# nRF_52840.net
KiCad netlist of a schematic drawn in Altium Designer
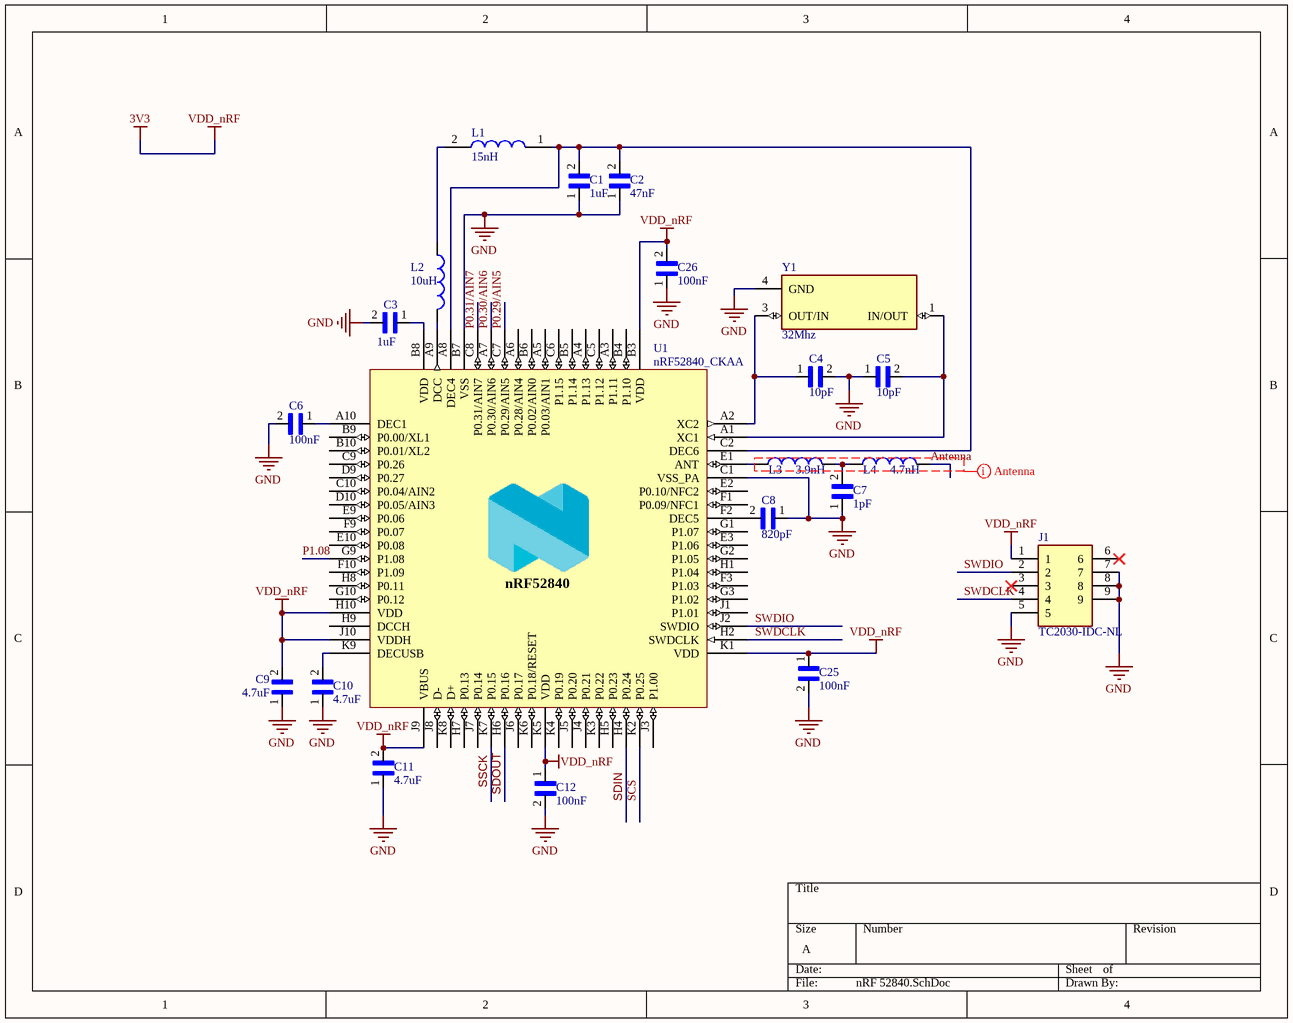
[diagram p0: nRF 52840.SchDoc]

(export (version "E")
  (design (tool "Eeschema 10.0.6"))
  (components
    (comp (ref "C1")
      (value "1uF")
      (footprint "CAPC1608X90N")
      (fields
        (field (name "MANUFACTURER") "TDK")
        (field (name "MANUFACTURER PART NUMBER") "C1608X7R1C105K080AC")
        (field (name "TOLERANCE") "10%")
      )
      (libsource (lib "SnapEDA_Library") (part "C1608X7R1C105K080AC"))
    )
    (comp (ref "C2")
      (value "47nF")
      (footprint "CAPC0603X33N")
      (description "0201 47 nF 16 V ±10% Tolerance X5R SMT Multilayer Ceramic Capacitor")
      (fields
        (field (name "MANUFACTURER") "Murata")
        (field (name "MANUFACTURER PART NUMBER") "GRM033R61C473KE84D")
      )
      (libsource (lib "SnapEDA_Library") (part "GRM033R61C473KE84D"))
    )
    (comp (ref "C3")
      (value "1uF")
      (footprint "CAPC1608X90N")
      (fields
        (field (name "MANUFACTURER") "TDK")
        (field (name "MANUFACTURER PART NUMBER") "C1608X7R1C105K080AC")
        (field (name "TOLERANCE") "10%")
      )
      (libsource (lib "") (part "C1608X7R1C105K080AC_1"))
    )
    (comp (ref "C4")
      (value "10pF")
      (footprint "CAPC0603X33N")
      (description "Cap Ceramic 10pF 100V C0G 5% Pad SMD 0201 125C T/R")
      (fields
        (field (name "MANUFACTURER") "Murata")
        (field (name "MANUFACTURER PART NUMBER") "GRM0335C2A100JA01D")
      )
      (libsource (lib "SnapEDA_Library") (part "GRM0335C2A100JA01D"))
    )
    (comp (ref "C5")
      (value "10pF")
      (footprint "CAPC0603X33N")
      (description "Cap Ceramic 10pF 100V C0G 5% Pad SMD 0201 125C T/R")
      (fields
        (field (name "MANUFACTURER") "Murata")
        (field (name "MANUFACTURER PART NUMBER") "GRM0335C2A100JA01D")
      )
      (libsource (lib "SnapEDA_Library") (part "GRM0335C2A100JA01D"))
    )
    (comp (ref "C6")
      (value "100nF")
      (footprint "CAPC1608X90N")
      (description "0603 100 nF 25 V -20 / +80 % Tolerance Y5V SMT Multilayer Ceramic Capacitor")
      (fields
        (field (name "MANUFACTURER") "Kyocera AVX")
        (field (name "MANUFACTURER PART NUMBER") "06033G104ZAT2A")
      )
      (libsource (lib "SnapEDA_Library") (part "06033G104ZAT2A"))
    )
    (comp (ref "C7")
      (value "1pF")
      (footprint "CAPC0603X33N")
      (description "0201 1 pF 50 V ±0.1 pF Tolerance C0G SMT Multilayer Ceramic Capacitor")
      (fields
        (field (name "MANUFACTURER") "Murata")
        (field (name "MANUFACTURER PART NUMBER") "GRM0335C1H1R0BA01D")
      )
      (libsource (lib "SnapEDA_Library") (part "GRM0335C1H1R0BA01D"))
    )
    (comp (ref "C8")
      (value "820pF")
      (footprint "CAPC0603X33N")
      (description "0201 820 pF 25 V ±10% Tolerance X7R Multilayer Ceramic Capacitor")
      (fields
        (field (name "MANUFACTURER") "Murata")
        (field (name "MANUFACTURER PART NUMBER") "GRM033R71E821KA01D")
      )
      (libsource (lib "SnapEDA_Library") (part "GRM033R71E821KA01D"))
    )
    (comp (ref "C9")
      (value "4.7uF")
      (footprint "CAPC1608X95N")
      (description "0603 4.7 uF 10 V ±10% Tolerance X7S Multilayer Ceramic Capacitor")
      (fields
        (field (name "MANUFACTURER") "Murata")
        (field (name "MANUFACTURER PART NUMBER") "GRM188C71A475KE11D")
      )
      (libsource (lib "SnapEDA_Library") (part "GRM188C71A475KE11D"))
    )
    (comp (ref "C10")
      (value "4.7uF")
      (footprint "CAPC1608X95N")
      (description "0603 4.7 uF 10 V ±10% Tolerance X7S Multilayer Ceramic Capacitor")
      (fields
        (field (name "MANUFACTURER") "Murata")
        (field (name "MANUFACTURER PART NUMBER") "GRM188C71A475KE11D")
      )
      (libsource (lib "SnapEDA_Library") (part "GRM188C71A475KE11D"))
    )
    (comp (ref "C11")
      (value "4.7uF")
      (footprint "CAPC1608X95N")
      (description "0603 4.7 uF 10 V ±10% Tolerance X7S Multilayer Ceramic Capacitor")
      (fields
        (field (name "MANUFACTURER") "Murata")
        (field (name "MANUFACTURER PART NUMBER") "GRM188C71A475KE11D")
      )
      (libsource (lib "SnapEDA_Library") (part "GRM188C71A475KE11D"))
    )
    (comp (ref "C12")
      (value "100nF")
      (footprint "CAPC1005X55N")
      (description "Cap Ceramic 0.1uF 25V X5R 10% Pad SMD 0402 85°C T/R / Multi Layer Ceramic Capacitor (MLCC)")
      (fields
        (field (name "MANUFACTURER") "Samsung")
        (field (name "MANUFACTURER PART NUMBER") "CL05A104KA5NNNC")
      )
      (libsource (lib "SnapEDA_Library") (part "CL05A104KA5NNNC"))
    )
    (comp (ref "C25")
      (value "100nF")
      (footprint "CAPC1005X55N")
      (description "Cap Ceramic 0.1uF 25V X5R 10% Pad SMD 0402 85°C T/R / Multi Layer Ceramic Capacitor (MLCC)")
      (fields
        (field (name "MANUFACTURER") "Samsung")
        (field (name "MANUFACTURER PART NUMBER") "CL05A104KA5NNNC")
      )
      (libsource (lib "SnapEDA_Library") (part "CL05A104KA5NNNC"))
    )
    (comp (ref "C26")
      (value "100nF")
      (footprint "CAPC1005X55N")
      (description "Cap Ceramic 0.1uF 25V X5R 10% Pad SMD 0402 85°C T/R / Multi Layer Ceramic Capacitor (MLCC)")
      (fields
        (field (name "MANUFACTURER") "Samsung")
        (field (name "MANUFACTURER PART NUMBER") "CL05A104KA5NNNC")
      )
      (libsource (lib "") (part "CL05A104KA5NNNC_1"))
    )
    (comp (ref "J1")
      (value "TC2030-IDC-NL")
      (footprint "SamacSys:TC2030IDCNL")
      (description "Connector")
      (libsource (lib "*") (part "TC2030-IDC-NL"))
    )
    (comp (ref "L1")
      (value "15nH")
      (footprint "SamacSys:LQG15WH0N7B02D")
      (description "Inductor RF Chip Multi-Layer 15nH 5% 100MHz 8Q-Factor Air 300mA 460mOhm DCR 0402 Paper T/R")
      (fields
        (field (name "MANUFACTURER") "Murata")
        (field (name "MANUFACTURER PART NUMBER") "LQG15HN15NJ02D")
      )
      (libsource (lib "*") (part "LQG15HN15NJ02D"))
    )
    (comp (ref "L2")
      (value "10uH")
      (footprint "INDC1608X100N")
      (description "Inductor Chip Wirewound 10uH 10% 2.52MHz Ferrite 80mA 468mOhm DCR 0603 T/R")
      (fields
        (field (name "MANUFACTURER") "Taiyo Yuden")
        (field (name "MANUFACTURER PART NUMBER") "LBMF1608T100K")
      )
      (libsource (lib "SnapEDA_Library") (part "LBMF1608T100K"))
    )
    (comp (ref "L3")
      (value "3.9nH")
      (footprint "INDC0603X33N")
      (description "Inductor RF Chip Thin Film 3.9nH 0.1nH 500MHz 14Q-Factor 400mA 300mOhm DCR 0201 Paper T/R")
      (fields
        (field (name "MANUFACTURER") "Murata")
        (field (name "MANUFACTURER PART NUMBER") "LQP03TN3N9B02D")
      )
      (libsource (lib "Flex PCB") (part "LQP03TN3N9B02D"))
    )
    (comp (ref "L4")
      (value "4.7nH")
      (footprint "INDC0603X33N")
      (description "Inductor RF Chip Thin Film 4.7nH 3% 500MHz 14Q-Factor 350mA 400mOhm DCR 0201 Paper T/R")
      (fields (field (name "MF") "{'manufacturer': u'Murata'}") (field (name "MANUFACTURER") "Murata"))
      (libsource (lib "Flex PCB") (part "LQP03TN4N7H02D"))
    )
    (comp (ref "U1")
      (value "nRF52840_CKAA")
      (footprint "BGA94C35P10X10_352X356X50")
      (description "Multi-protocol Bluetooth Low Energy, IEEE 802.15.4, ANT and 2.4GHz proprietary system-on-chip")
      (fields
        (field (name "MANUFACTURER") "Nordic Semiconductor")
        (field (name "MANUFACTURER PART NUMBER") "nRF52840-CKAAD0")
        (field (name "PUBLISHER") "Nordic Semiconductor")
      )
      (libsource (lib "nrf52840_ckaa") (part "nRF52840_CKAA"))
    )
    (comp (ref "Y1")
      (value "32Mhz")
      (footprint "XTAL_ECS-374-8-48-CKY-TR")
      (description "Crystal 32MHz ±10ppm (Tol) ±10ppm (Stability) 10pF 100Ohm 4-Pin Ultra Mini-CSMD T/R")
      (fields
        (field (name "MANUFACTURER") "ECS International")
        (field (name "MANUFACTURER PART NUMBER") "ECS-320-10-48-CKY-TR")
      )
      (libsource (lib "SnapEDA_Library") (part "ECS-320-10-48-CKY-TR"))
    )
  )
  (nets
    (net (code "1") (name "/Antenna") (class "Default")
      (node (ref "L4") (pin "2") (pinfunction "2_2") (pintype "passive"))
    )
    (net (code "2") (name "/P0.29{slash}AIN5") (class "Default")
      (node (ref "U1") (pin "C7") (pinfunction "P0.29/AIN5_C7") (pintype "bidirectional"))
    )
    (net (code "3") (name "/P0.30{slash}AIN6") (class "Default")
      (node (ref "U1") (pin "A7") (pinfunction "P0.30/AIN6_A7") (pintype "bidirectional"))
    )
    (net (code "4") (name "/P0.31{slash}AIN7") (class "Default")
      (node (ref "U1") (pin "C8") (pinfunction "P0.31/AIN7_C8") (pintype "bidirectional"))
    )
    (net (code "5") (name "/P1.08") (class "Default")
      (node (ref "U1") (pin "G9") (pinfunction "P1.08_G9") (pintype "bidirectional"))
    )
    (net (code "6") (name "/SCS") (class "Default")
      (node (ref "U1") (pin "K2") (pinfunction "P0.25_K2") (pintype "bidirectional"))
    )
    (net (code "7") (name "/SDIN") (class "Default")
      (node (ref "U1") (pin "H4") (pinfunction "P0.24_H4") (pintype "bidirectional"))
    )
    (net (code "8") (name "/SDOUT") (class "Default")
      (node (ref "U1") (pin "H6") (pinfunction "P0.16_H6") (pintype "bidirectional"))
    )
    (net (code "9") (name "/SSCK") (class "Default")
      (node (ref "U1") (pin "K7") (pinfunction "P0.15_K7") (pintype "bidirectional"))
    )
    (net (code "10") (name "/SWDCLK") (class "Default")
      (node (ref "J1") (pin "4") (pinfunction "4_4") (pintype "passive"))
      (node (ref "U1") (pin "H2") (pinfunction "SWDCLK_H2") (pintype "input"))
    )
    (net (code "11") (name "/SWDIO") (class "Default")
      (node (ref "J1") (pin "2") (pinfunction "2_2") (pintype "passive"))
      (node (ref "U1") (pin "J2") (pinfunction "SWDIO_J2") (pintype "bidirectional"))
    )
    (net (code "12") (name "3V3") (class "Default")
      (node (ref "C11") (pin "2") (pinfunction "2_2") (pintype "passive"))
      (node (ref "C12") (pin "1") (pinfunction "1_1") (pintype "passive"))
      (node (ref "C25") (pin "1") (pinfunction "1_1") (pintype "passive"))
      (node (ref "C26") (pin "2") (pinfunction "2_2") (pintype "passive"))
      (node (ref "C9") (pin "2") (pinfunction "2_2") (pintype "passive"))
      (node (ref "J1") (pin "1") (pinfunction "1_1") (pintype "passive"))
      (node (ref "U1") (pin "B3") (pinfunction "VDD_B3") (pintype "power_in"))
      (node (ref "U1") (pin "H10") (pinfunction "VDD_H10") (pintype "power_in"))
      (node (ref "U1") (pin "J10") (pinfunction "VDDH_J10") (pintype "power_in"))
      (node (ref "U1") (pin "J9") (pinfunction "VBUS_J9") (pintype "power_in"))
      (node (ref "U1") (pin "K1") (pinfunction "VDD_K1") (pintype "power_in"))
      (node (ref "U1") (pin "K5") (pinfunction "VDD_K5") (pintype "power_in"))
    )
    (net (code "13") (name "GND") (class "Default")
      (node (ref "C1") (pin "1") (pinfunction "1_1") (pintype "passive"))
      (node (ref "C10") (pin "1") (pinfunction "1_1") (pintype "passive"))
      (node (ref "C11") (pin "1") (pinfunction "1_1") (pintype "passive"))
      (node (ref "C12") (pin "2") (pinfunction "2_2") (pintype "passive"))
      (node (ref "C2") (pin "1") (pinfunction "1_1") (pintype "passive"))
      (node (ref "C25") (pin "2") (pinfunction "2_2") (pintype "passive"))
      (node (ref "C26") (pin "1") (pinfunction "1_1") (pintype "passive"))
      (node (ref "C3") (pin "2") (pinfunction "2_2") (pintype "passive"))
      (node (ref "C4") (pin "2") (pinfunction "2_2") (pintype "passive"))
      (node (ref "C5") (pin "1") (pinfunction "1_1") (pintype "passive"))
      (node (ref "C6") (pin "2") (pinfunction "2_2") (pintype "passive"))
      (node (ref "C7") (pin "1") (pinfunction "1_1") (pintype "passive"))
      (node (ref "C8") (pin "1") (pinfunction "1_1") (pintype "passive"))
      (node (ref "C9") (pin "1") (pinfunction "1_1") (pintype "passive"))
      (node (ref "J1") (pin "5") (pinfunction "5_5") (pintype "passive"))
      (node (ref "J1") (pin "7") (pinfunction "7_7") (pintype "passive"))
      (node (ref "J1") (pin "8") (pinfunction "8_8") (pintype "passive"))
      (node (ref "J1") (pin "9") (pinfunction "9_9") (pintype "passive"))
      (node (ref "U1") (pin "B7") (pinfunction "VSS_B7") (pintype "power_in"))
      (node (ref "U1") (pin "C1") (pinfunction "VSS_PA_C1") (pintype "power_in"))
      (node (ref "U1") (pin "C4") (pinfunction "GND_C4") (pintype "power_in"))
      (node (ref "U1") (pin "D3") (pinfunction "GND_D3") (pintype "power_in"))
      (node (ref "U1") (pin "D4") (pinfunction "GND_D4") (pintype "power_in"))
      (node (ref "U1") (pin "D5") (pinfunction "GND_D5") (pintype "power_in"))
      (node (ref "U1") (pin "D6") (pinfunction "GND_D6") (pintype "power_in"))
      (node (ref "U1") (pin "D7") (pinfunction "GND_D7") (pintype "power_in"))
      (node (ref "U1") (pin "D8") (pinfunction "GND_D8") (pintype "power_in"))
      (node (ref "U1") (pin "E4") (pinfunction "GND_E4") (pintype "power_in"))
      (node (ref "U1") (pin "E5") (pinfunction "GND_E5") (pintype "power_in"))
      (node (ref "U1") (pin "E6") (pinfunction "GND_E6") (pintype "power_in"))
      (node (ref "U1") (pin "E7") (pinfunction "GND_E7") (pintype "power_in"))
      (node (ref "U1") (pin "E8") (pinfunction "GND_E8") (pintype "power_in"))
      (node (ref "U1") (pin "F4") (pinfunction "GND_F4") (pintype "power_in"))
      (node (ref "U1") (pin "F5") (pinfunction "GND_F5") (pintype "power_in"))
      (node (ref "U1") (pin "F6") (pinfunction "GND_F6") (pintype "power_in"))
      (node (ref "U1") (pin "F7") (pinfunction "GND_F7") (pintype "power_in"))
      (node (ref "U1") (pin "F8") (pinfunction "GND_F8") (pintype "power_in"))
      (node (ref "U1") (pin "G4") (pinfunction "GND_G4") (pintype "power_in"))
      (node (ref "U1") (pin "G5") (pinfunction "GND_G5") (pintype "power_in"))
      (node (ref "U1") (pin "G6") (pinfunction "GND_G6") (pintype "power_in"))
      (node (ref "U1") (pin "G7") (pinfunction "GND_G7") (pintype "power_in"))
      (node (ref "U1") (pin "G8") (pinfunction "GND_G8") (pintype "power_in"))
      (node (ref "U1") (pin "K10") (pinfunction "GND_K10") (pintype "power_in"))
      (node (ref "Y1") (pin "4") (pinfunction "GND_4") (pintype "power_in"))
    )
    (net (code "14") (name "Net-(C3-Pad1)") (class "Default")
      (node (ref "C3") (pin "1") (pinfunction "1_1") (pintype "passive"))
      (node (ref "U1") (pin "B8") (pinfunction "VDD_B8") (pintype "power_in"))
    )
    (net (code "15") (name "Net-(C7-Pad2)") (class "Default")
      (node (ref "C7") (pin "2") (pinfunction "2_2") (pintype "passive"))
      (node (ref "L3") (pin "2") (pinfunction "2_2") (pintype "passive"))
      (node (ref "L4") (pin "1") (pinfunction "1_1") (pintype "passive"))
    )
    (net (code "16") (name "Net-(L1-Pad2)") (class "Default")
      (node (ref "L1") (pin "2") (pinfunction "2_2") (pintype "passive"))
      (node (ref "L2") (pin "1") (pinfunction "1_1") (pintype "passive"))
    )
    (net (code "17") (name "Net-(U1-ANT)") (class "Default")
      (node (ref "L3") (pin "1") (pinfunction "1_1") (pintype "passive"))
      (node (ref "U1") (pin "E1") (pinfunction "ANT_E1") (pintype "bidirectional"))
    )
    (net (code "18") (name "Net-(U1-DCC)") (class "Default")
      (node (ref "L2") (pin "2") (pinfunction "2_2") (pintype "passive"))
      (node (ref "U1") (pin "A9") (pinfunction "DCC_A9") (pintype "output"))
    )
    (net (code "19") (name "Net-(U1-DEC1)") (class "Default")
      (node (ref "C6") (pin "1") (pinfunction "1_1") (pintype "passive"))
      (node (ref "U1") (pin "A10") (pinfunction "DEC1_A10") (pintype "power_in"))
    )
    (net (code "20") (name "Net-(U1-DEC4)") (class "Default")
      (node (ref "C1") (pin "2") (pinfunction "2_2") (pintype "passive"))
      (node (ref "C2") (pin "2") (pinfunction "2_2") (pintype "passive"))
      (node (ref "L1") (pin "1") (pinfunction "1_1") (pintype "passive"))
      (node (ref "U1") (pin "A8") (pinfunction "DEC4_A8") (pintype "power_in"))
      (node (ref "U1") (pin "C2") (pinfunction "DEC6_C2") (pintype "power_in"))
    )
    (net (code "21") (name "Net-(U1-DEC5)") (class "Default")
      (node (ref "C8") (pin "2") (pinfunction "2_2") (pintype "passive"))
      (node (ref "U1") (pin "F2") (pinfunction "DEC5_F2") (pintype "power_in"))
    )
    (net (code "22") (name "Net-(U1-DECUSB)") (class "Default")
      (node (ref "C10") (pin "2") (pinfunction "2_2") (pintype "passive"))
      (node (ref "U1") (pin "K9") (pinfunction "DECUSB_K9") (pintype "power_in"))
    )
    (net (code "23") (name "Net-(U1-XC1)") (class "Default")
      (node (ref "C5") (pin "2") (pinfunction "2_2") (pintype "passive"))
      (node (ref "U1") (pin "A1") (pinfunction "XC1_A1") (pintype "input"))
      (node (ref "Y1") (pin "1") (pinfunction "IN/OUT_1") (pintype "bidirectional"))
    )
    (net (code "24") (name "Net-(U1-XC2)") (class "Default")
      (node (ref "C4") (pin "1") (pinfunction "1_1") (pintype "passive"))
      (node (ref "U1") (pin "A2") (pinfunction "XC2_A2") (pintype "output"))
      (node (ref "Y1") (pin "3") (pinfunction "OUT/IN_3") (pintype "bidirectional"))
    )
    (net (code "25") (name "unconnected-(J1-Pad3)") (class "Default")
      (node (ref "J1") (pin "3") (pinfunction "3_3") (pintype "passive+no_connect"))
    )
    (net (code "26") (name "unconnected-(J1-Pad6)") (class "Default")
      (node (ref "J1") (pin "6") (pinfunction "6_6") (pintype "passive+no_connect"))
    )
    (net (code "27") (name "unconnected-(U1-D+-PadK8)") (class "Default")
      (node (ref "U1") (pin "K8") (pinfunction "D+_K8") (pintype "bidirectional"))
    )
    (net (code "28") (name "unconnected-(U1-D--PadJ8)") (class "Default")
      (node (ref "U1") (pin "J8") (pinfunction "D-_J8") (pintype "bidirectional"))
    )
    (net (code "29") (name "unconnected-(U1-DCCH-PadH9)") (class "Default")
      (node (ref "U1") (pin "H9") (pinfunction "DCCH_H9") (pintype "power_in"))
    )
    (net (code "30") (name "unconnected-(U1-P0.00{slash}XL1-PadB9)") (class "Default")
      (node (ref "U1") (pin "B9") (pinfunction "P0.00/XL1_B9") (pintype "bidirectional"))
    )
    (net (code "31") (name "unconnected-(U1-P0.01{slash}XL2-PadB10)") (class "Default")
      (node (ref "U1") (pin "B10") (pinfunction "P0.01/XL2_B10") (pintype "bidirectional"))
    )
    (net (code "32") (name "unconnected-(U1-P0.02{slash}AIN0-PadB6)") (class "Default")
      (node (ref "U1") (pin "B6") (pinfunction "P0.02/AIN0_B6") (pintype "bidirectional"))
    )
    (net (code "33") (name "unconnected-(U1-P0.03{slash}AIN1-PadA5)") (class "Default")
      (node (ref "U1") (pin "A5") (pinfunction "P0.03/AIN1_A5") (pintype "bidirectional"))
    )
    (net (code "34") (name "unconnected-(U1-P0.04{slash}AIN2-PadC10)") (class "Default")
      (node (ref "U1") (pin "C10") (pinfunction "P0.04/AIN2_C10") (pintype "bidirectional"))
    )
    (net (code "35") (name "unconnected-(U1-P0.05{slash}AIN3-PadD10)") (class "Default")
      (node (ref "U1") (pin "D10") (pinfunction "P0.05/AIN3_D10") (pintype "bidirectional"))
    )
    (net (code "36") (name "unconnected-(U1-P0.06-PadE9)") (class "Default")
      (node (ref "U1") (pin "E9") (pinfunction "P0.06_E9") (pintype "bidirectional"))
    )
    (net (code "37") (name "unconnected-(U1-P0.07-PadF9)") (class "Default")
      (node (ref "U1") (pin "F9") (pinfunction "P0.07_F9") (pintype "bidirectional"))
    )
    (net (code "38") (name "unconnected-(U1-P0.08-PadE10)") (class "Default")
      (node (ref "U1") (pin "E10") (pinfunction "P0.08_E10") (pintype "bidirectional"))
    )
    (net (code "39") (name "unconnected-(U1-P0.09{slash}NFC1-PadF1)") (class "Default")
      (node (ref "U1") (pin "F1") (pinfunction "P0.09/NFC1_F1") (pintype "bidirectional"))
    )
    (net (code "40") (name "unconnected-(U1-P0.10{slash}NFC2-PadE2)") (class "Default")
      (node (ref "U1") (pin "E2") (pinfunction "P0.10/NFC2_E2") (pintype "bidirectional"))
    )
    (net (code "41") (name "unconnected-(U1-P0.11-PadH8)") (class "Default")
      (node (ref "U1") (pin "H8") (pinfunction "P0.11_H8") (pintype "bidirectional"))
    )
    (net (code "42") (name "unconnected-(U1-P0.12-PadG10)") (class "Default")
      (node (ref "U1") (pin "G10") (pinfunction "P0.12_G10") (pintype "bidirectional"))
    )
    (net (code "43") (name "unconnected-(U1-P0.13-PadH7)") (class "Default")
      (node (ref "U1") (pin "H7") (pinfunction "P0.13_H7") (pintype "bidirectional"))
    )
    (net (code "44") (name "unconnected-(U1-P0.14-PadJ7)") (class "Default")
      (node (ref "U1") (pin "J7") (pinfunction "P0.14_J7") (pintype "bidirectional"))
    )
    (net (code "45") (name "unconnected-(U1-P0.17-PadJ6)") (class "Default")
      (node (ref "U1") (pin "J6") (pinfunction "P0.17_J6") (pintype "bidirectional"))
    )
    (net (code "46") (name "unconnected-(U1-P0.18{slash}RESET-PadK6)") (class "Default")
      (node (ref "U1") (pin "K6") (pinfunction "P0.18/RESET_K6") (pintype "bidirectional"))
    )
    (net (code "47") (name "unconnected-(U1-P0.19-PadK4)") (class "Default")
      (node (ref "U1") (pin "K4") (pinfunction "P0.19_K4") (pintype "bidirectional"))
    )
    (net (code "48") (name "unconnected-(U1-P0.20-PadJ5)") (class "Default")
      (node (ref "U1") (pin "J5") (pinfunction "P0.20_J5") (pintype "bidirectional"))
    )
    (net (code "49") (name "unconnected-(U1-P0.21-PadJ4)") (class "Default")
      (node (ref "U1") (pin "J4") (pinfunction "P0.21_J4") (pintype "bidirectional"))
    )
    (net (code "50") (name "unconnected-(U1-P0.22-PadK3)") (class "Default")
      (node (ref "U1") (pin "K3") (pinfunction "P0.22_K3") (pintype "bidirectional"))
    )
    (net (code "51") (name "unconnected-(U1-P0.23-PadH5)") (class "Default")
      (node (ref "U1") (pin "H5") (pinfunction "P0.23_H5") (pintype "bidirectional"))
    )
    (net (code "52") (name "unconnected-(U1-P0.26-PadC9)") (class "Default")
      (node (ref "U1") (pin "C9") (pinfunction "P0.26_C9") (pintype "bidirectional"))
    )
    (net (code "53") (name "unconnected-(U1-P0.27-PadD9)") (class "Default")
      (node (ref "U1") (pin "D9") (pinfunction "P0.27_D9") (pintype "bidirectional"))
    )
    (net (code "54") (name "unconnected-(U1-P0.28{slash}AIN4-PadA6)") (class "Default")
      (node (ref "U1") (pin "A6") (pinfunction "P0.28/AIN4_A6") (pintype "bidirectional"))
    )
    (net (code "55") (name "unconnected-(U1-P1.00-PadJ3)") (class "Default")
      (node (ref "U1") (pin "J3") (pinfunction "P1.00_J3") (pintype "bidirectional"))
    )
    (net (code "56") (name "unconnected-(U1-P1.01-PadJ1)") (class "Default")
      (node (ref "U1") (pin "J1") (pinfunction "P1.01_J1") (pintype "bidirectional"))
    )
    (net (code "57") (name "unconnected-(U1-P1.02-PadG3)") (class "Default")
      (node (ref "U1") (pin "G3") (pinfunction "P1.02_G3") (pintype "bidirectional"))
    )
    (net (code "58") (name "unconnected-(U1-P1.03-PadF3)") (class "Default")
      (node (ref "U1") (pin "F3") (pinfunction "P1.03_F3") (pintype "bidirectional"))
    )
    (net (code "59") (name "unconnected-(U1-P1.04-PadH1)") (class "Default")
      (node (ref "U1") (pin "H1") (pinfunction "P1.04_H1") (pintype "bidirectional"))
    )
    (net (code "60") (name "unconnected-(U1-P1.05-PadG2)") (class "Default")
      (node (ref "U1") (pin "G2") (pinfunction "P1.05_G2") (pintype "bidirectional"))
    )
    (net (code "61") (name "unconnected-(U1-P1.06-PadE3)") (class "Default")
      (node (ref "U1") (pin "E3") (pinfunction "P1.06_E3") (pintype "bidirectional"))
    )
    (net (code "62") (name "unconnected-(U1-P1.07-PadG1)") (class "Default")
      (node (ref "U1") (pin "G1") (pinfunction "P1.07_G1") (pintype "bidirectional"))
    )
    (net (code "63") (name "unconnected-(U1-P1.09-PadF10)") (class "Default")
      (node (ref "U1") (pin "F10") (pinfunction "P1.09_F10") (pintype "bidirectional"))
    )
    (net (code "64") (name "unconnected-(U1-P1.10-PadB4)") (class "Default")
      (node (ref "U1") (pin "B4") (pinfunction "P1.10_B4") (pintype "bidirectional"))
    )
    (net (code "65") (name "unconnected-(U1-P1.11-PadA3)") (class "Default")
      (node (ref "U1") (pin "A3") (pinfunction "P1.11_A3") (pintype "bidirectional"))
    )
    (net (code "66") (name "unconnected-(U1-P1.12-PadC5)") (class "Default")
      (node (ref "U1") (pin "C5") (pinfunction "P1.12_C5") (pintype "bidirectional"))
    )
    (net (code "67") (name "unconnected-(U1-P1.13-PadA4)") (class "Default")
      (node (ref "U1") (pin "A4") (pinfunction "P1.13_A4") (pintype "bidirectional"))
    )
    (net (code "68") (name "unconnected-(U1-P1.14-PadB5)") (class "Default")
      (node (ref "U1") (pin "B5") (pinfunction "P1.14_B5") (pintype "bidirectional"))
    )
    (net (code "69") (name "unconnected-(U1-P1.15-PadC6)") (class "Default")
      (node (ref "U1") (pin "C6") (pinfunction "P1.15_C6") (pintype "bidirectional"))
    )
  )
)
